# MayKhoan.net
KiCad netlist of a schematic drawn in EasyEDA Pro
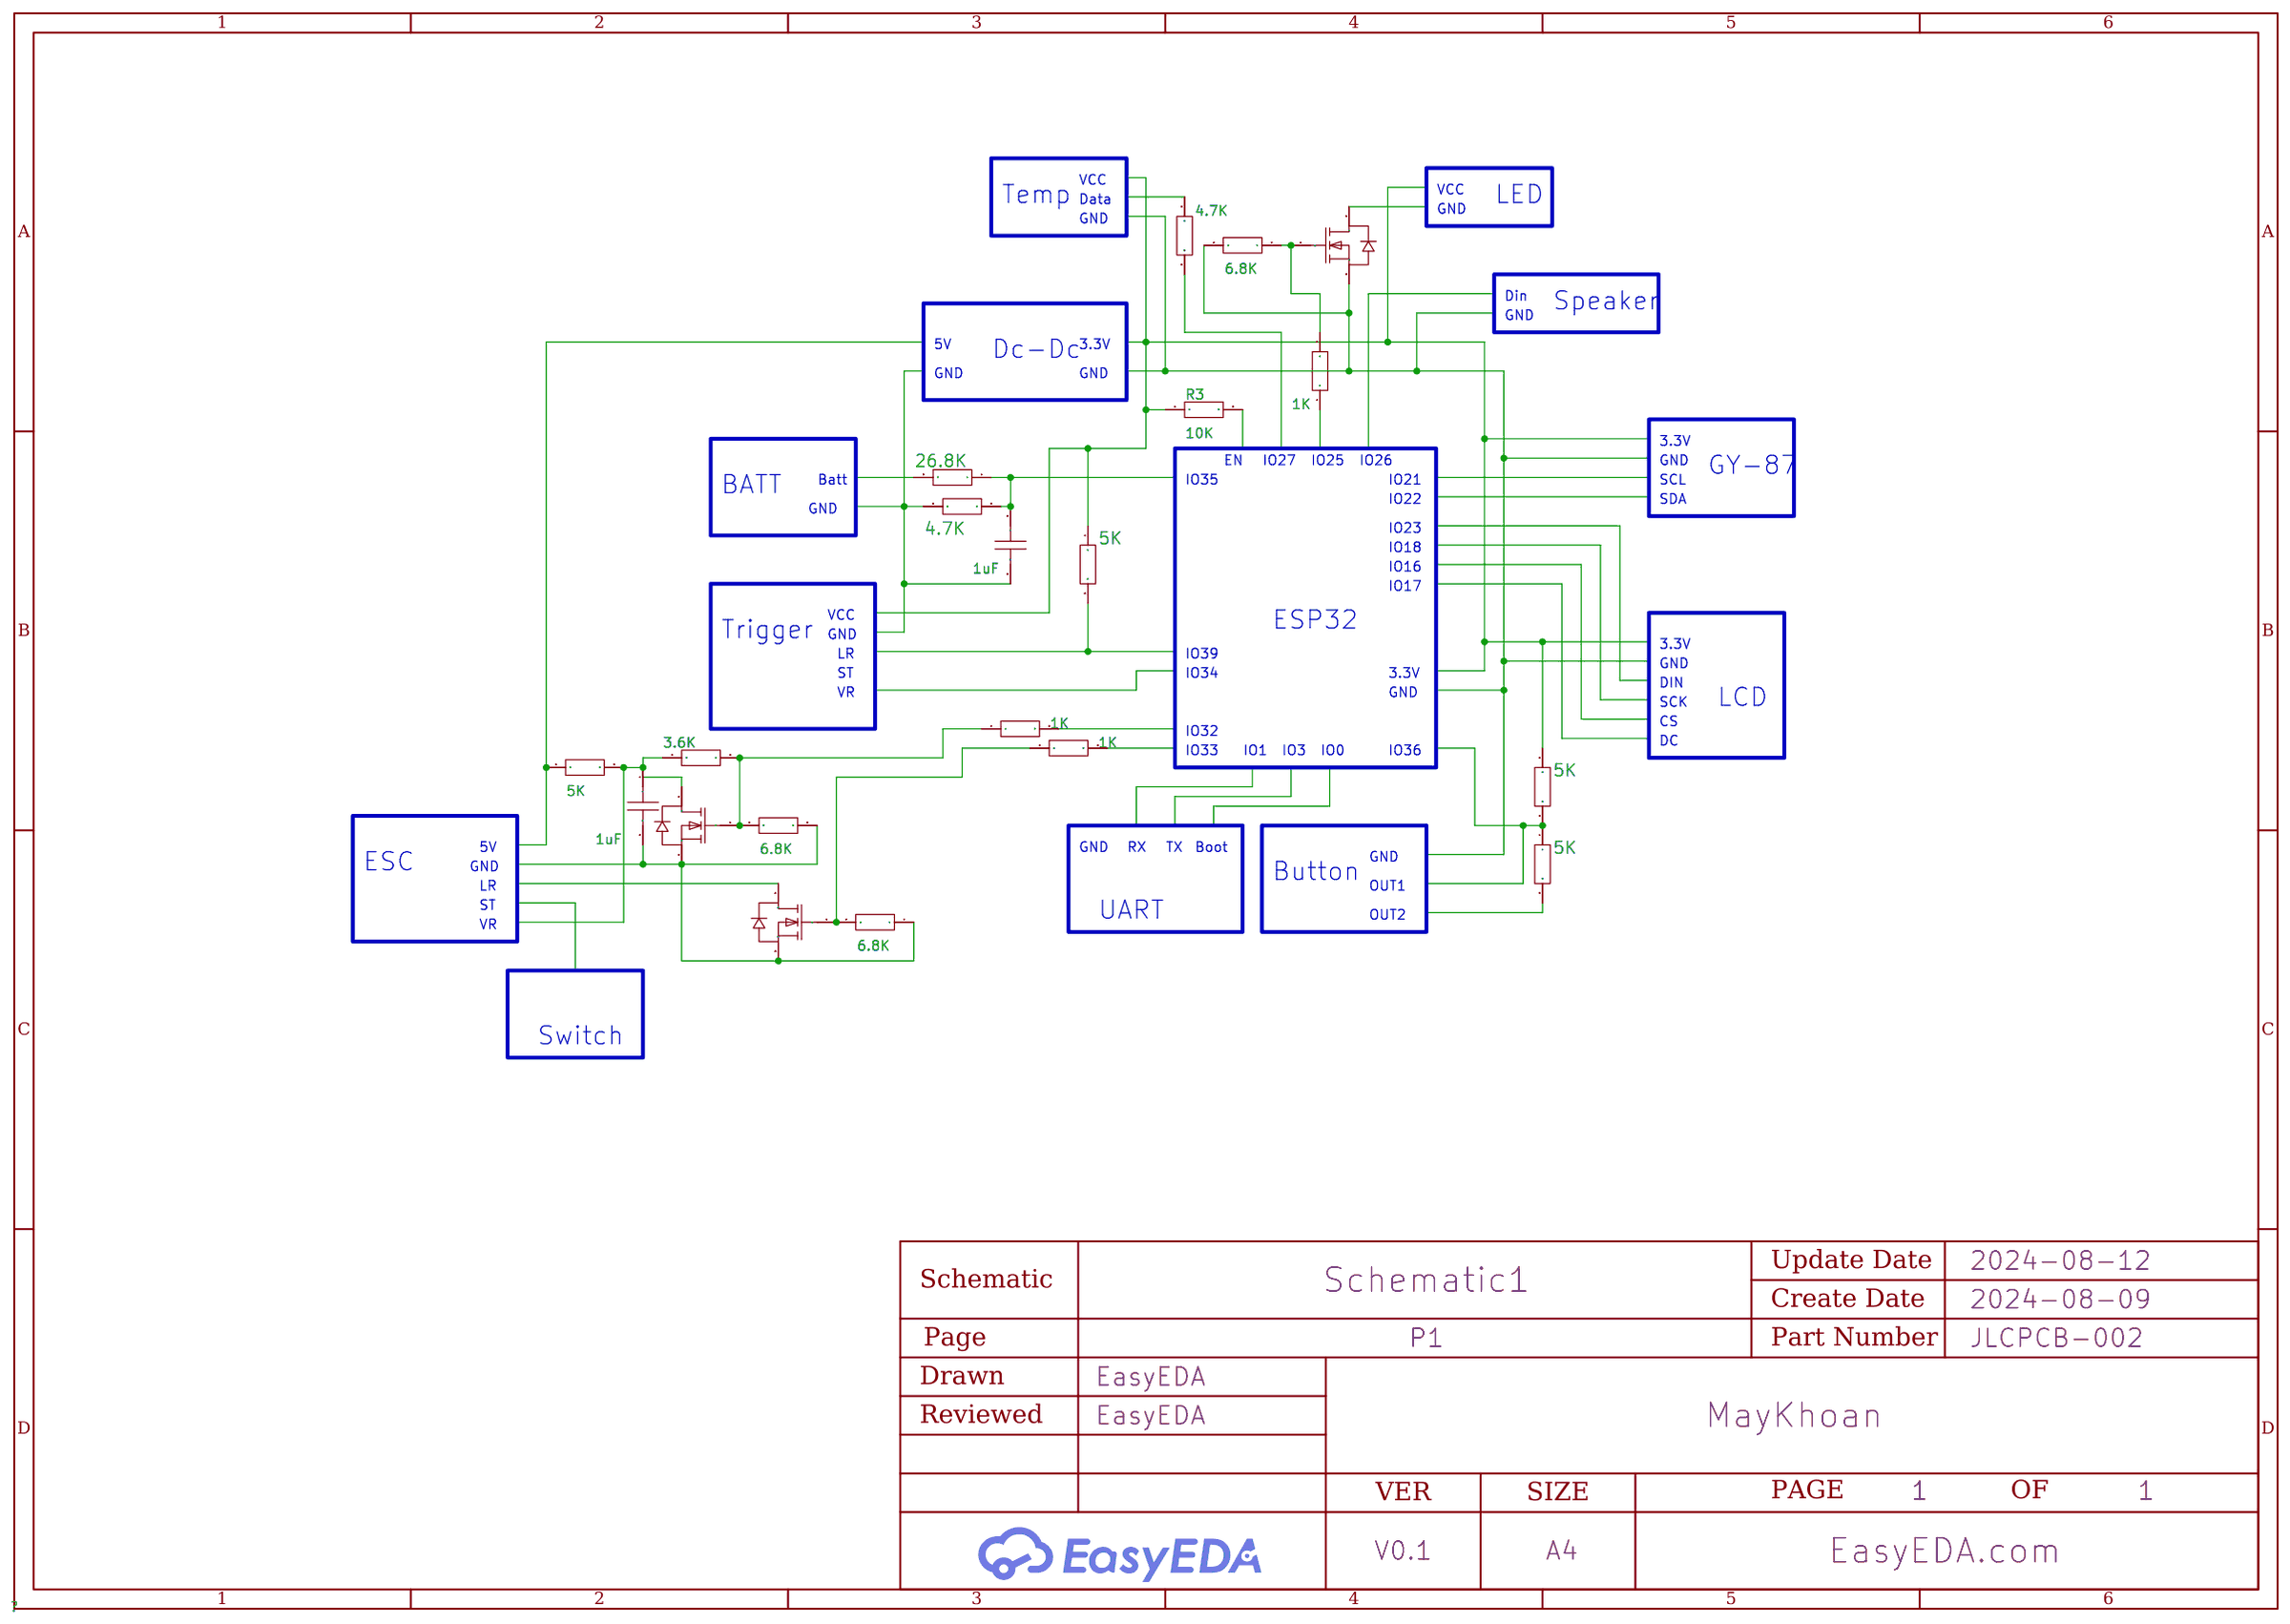
[diagram p0: schematic sheet]

(export (version "E")
  (design (tool "Eeschema 10.0.6"))
  (components
    (comp (ref "C1") (value "1uF") (footprint "easyedapro:C0603") (libsource (lib "easyedapro") (part "CAP")))
    (comp (ref "C2") (value "1uF") (footprint "easyedapro:C0603") (libsource (lib "easyedapro") (part "CAP")))
    (comp (ref "R1")
      (value "4.7K")
      (footprint "easyedapro:R0603")
      (libsource (lib "easyedapro") (part "Res"))
    )
    (comp (ref "R2")
      (value "26.8K")
      (footprint "easyedapro:R0603")
      (libsource (lib "easyedapro") (part "Res"))
    )
    (comp (ref "R3") (value "10K") (footprint "easyedapro:R0603") (libsource (lib "easyedapro") (part "Res")))
    (comp (ref "R4") (value "5K") (footprint "easyedapro:R0603") (libsource (lib "easyedapro") (part "Res")))
    (comp (ref "R5")
      (value "3.6K")
      (footprint "easyedapro:R0603")
      (libsource (lib "easyedapro") (part "Res"))
    )
    (comp (ref "R6") (value "5K") (footprint "easyedapro:R0603") (libsource (lib "easyedapro") (part "Res")))
    (comp (ref "R7")
      (value "6.8K")
      (footprint "easyedapro:R0603")
      (libsource (lib "easyedapro") (part "Res"))
    )
    (comp (ref "R8")
      (value "6.8K")
      (footprint "easyedapro:R0603")
      (libsource (lib "easyedapro") (part "Res"))
    )
    (comp (ref "R10") (value "5K") (footprint "easyedapro:R0603") (libsource (lib "easyedapro") (part "Res")))
    (comp (ref "R11") (value "5K") (footprint "easyedapro:R0603") (libsource (lib "easyedapro") (part "Res")))
    (comp (ref "R12")
      (value "6.8K")
      (footprint "easyedapro:R0603")
      (libsource (lib "easyedapro") (part "Res"))
    )
    (comp (ref "R14") (value "1K") (footprint "easyedapro:R0603") (libsource (lib "easyedapro") (part "Res")))
    (comp (ref "R15") (value "1K") (footprint "easyedapro:R0603") (libsource (lib "easyedapro") (part "Res")))
    (comp (ref "R16") (value "1K") (footprint "easyedapro:R0603") (libsource (lib "easyedapro") (part "Res")))
    (comp (ref "R17")
      (value "4.7K")
      (footprint "easyedapro:R0603")
      (libsource (lib "easyedapro") (part "Res"))
    )
    (comp (ref "U1")
      (value "GC2M0080120D")
      (footprint "easyedapro:TO-247-3_L15.8-W5.0-P5.44-L")
      (fields (field (name "Manufacturer") "SUPSiC(国晶微半导体)"))
      (libsource (lib "easyedapro") (part "GC2M0080120D"))
    )
    (comp (ref "U2")
      (value "GC2M0080120D")
      (footprint "easyedapro:TO-247-3_L15.8-W5.0-P5.44-L")
      (fields (field (name "Manufacturer") "SUPSiC(国晶微半导体)"))
      (libsource (lib "easyedapro") (part "GC2M0080120D"))
    )
    (comp (ref "U4")
      (value "GC2M0080120D")
      (footprint "easyedapro:TO-247-3_L15.8-W5.0-P5.44-L")
      (fields (field (name "Manufacturer") "SUPSiC(国晶微半导体)"))
      (libsource (lib "easyedapro") (part "GC2M0080120D"))
    )
  )
  (nets
    (net (code "1") (name "Net-(C2-Pad1)") (class "Default")
      (node (ref "C2") (pin "1") (pinfunction "1_1") (pintype "input"))
      (node (ref "R1") (pin "1") (pinfunction "1_1") (pintype "input"))
      (node (ref "R2") (pin "1") (pinfunction "1_1") (pintype "input"))
    )
    (net (code "2") (name "Net-(C2-Pad2)") (class "Default")
      (node (ref "C2") (pin "2") (pinfunction "2_2") (pintype "input"))
      (node (ref "R1") (pin "2") (pinfunction "2_2") (pintype "input"))
    )
    (net (code "3") (name "Net-(R10-Pad1)") (class "Default")
      (node (ref "R10") (pin "1") (pinfunction "1_1") (pintype "input"))
      (node (ref "R11") (pin "2") (pinfunction "2_2") (pintype "input"))
    )
    (net (code "4") (name "Net-(R11-Pad1)") (class "Default")
      (node (ref "R11") (pin "1") (pinfunction "1_1") (pintype "input"))
      (node (ref "R3") (pin "1") (pinfunction "1_1") (pintype "input"))
      (node (ref "R4") (pin "1") (pinfunction "1_1") (pintype "input"))
    )
    (net (code "5") (name "Net-(U1-G)") (class "Default")
      (node (ref "R14") (pin "1") (pinfunction "1_1") (pintype "input"))
      (node (ref "R8") (pin "2") (pinfunction "2_2") (pintype "input"))
      (node (ref "U1") (pin "1") (pinfunction "G_1") (pintype "unspecified"))
    )
    (net (code "6") (name "Net-(U1-S)") (class "Default")
      (node (ref "C1") (pin "2") (pinfunction "2_2") (pintype "input"))
      (node (ref "R7") (pin "1") (pinfunction "1_1") (pintype "input"))
      (node (ref "R8") (pin "1") (pinfunction "1_1") (pintype "input"))
      (node (ref "U1") (pin "3") (pinfunction "S_3") (pintype "unspecified"))
      (node (ref "U2") (pin "3") (pinfunction "S_3") (pintype "unspecified"))
    )
    (net (code "7") (name "Net-(U2-D)") (class "Default")
      (node (ref "C1") (pin "1") (pinfunction "1_1") (pintype "input"))
      (node (ref "R5") (pin "1") (pinfunction "1_1") (pintype "input"))
      (node (ref "R6") (pin "2") (pinfunction "2_2") (pintype "input"))
      (node (ref "U2") (pin "2") (pinfunction "D_2") (pintype "unspecified"))
    )
    (net (code "8") (name "Net-(U2-G)") (class "Default")
      (node (ref "R15") (pin "1") (pinfunction "1_1") (pintype "input"))
      (node (ref "R5") (pin "2") (pinfunction "2_2") (pintype "input"))
      (node (ref "R7") (pin "2") (pinfunction "2_2") (pintype "input"))
      (node (ref "U2") (pin "1") (pinfunction "G_1") (pintype "unspecified"))
    )
    (net (code "9") (name "Net-(U4-G)") (class "Default")
      (node (ref "R12") (pin "1") (pinfunction "1_1") (pintype "input"))
      (node (ref "R16") (pin "2") (pinfunction "2_2") (pintype "input"))
      (node (ref "U4") (pin "1") (pinfunction "G_1") (pintype "unspecified"))
    )
    (net (code "10") (name "Net-(U4-S)") (class "Default")
      (node (ref "R12") (pin "2") (pinfunction "2_2") (pintype "input"))
      (node (ref "U4") (pin "3") (pinfunction "S_3") (pintype "unspecified"))
    )
    (net (code "11") (name "unconnected-(R2-Pad2)") (class "Default")
      (node (ref "R2") (pin "2") (pinfunction "2_2") (pintype "input"))
    )
    (net (code "12") (name "unconnected-(R3-Pad2)") (class "Default")
      (node (ref "R3") (pin "2") (pinfunction "2_2") (pintype "input"))
    )
    (net (code "13") (name "unconnected-(R4-Pad2)") (class "Default")
      (node (ref "R4") (pin "2") (pinfunction "2_2") (pintype "input"))
    )
    (net (code "14") (name "unconnected-(R6-Pad1)") (class "Default")
      (node (ref "R6") (pin "1") (pinfunction "1_1") (pintype "input"))
    )
    (net (code "15") (name "unconnected-(R10-Pad2)") (class "Default")
      (node (ref "R10") (pin "2") (pinfunction "2_2") (pintype "input"))
    )
    (net (code "16") (name "unconnected-(R14-Pad2)") (class "Default")
      (node (ref "R14") (pin "2") (pinfunction "2_2") (pintype "input"))
    )
    (net (code "17") (name "unconnected-(R15-Pad2)") (class "Default")
      (node (ref "R15") (pin "2") (pinfunction "2_2") (pintype "input"))
    )
    (net (code "18") (name "unconnected-(R16-Pad1)") (class "Default")
      (node (ref "R16") (pin "1") (pinfunction "1_1") (pintype "input"))
    )
    (net (code "19") (name "unconnected-(R17-Pad1)") (class "Default")
      (node (ref "R17") (pin "1") (pinfunction "1_1") (pintype "input"))
    )
    (net (code "20") (name "unconnected-(R17-Pad2)") (class "Default")
      (node (ref "R17") (pin "2") (pinfunction "2_2") (pintype "input"))
    )
    (net (code "21") (name "unconnected-(U1-D-Pad2)") (class "Default")
      (node (ref "U1") (pin "2") (pinfunction "D_2") (pintype "unspecified"))
    )
    (net (code "22") (name "unconnected-(U4-D-Pad2)") (class "Default")
      (node (ref "U4") (pin "2") (pinfunction "D_2") (pintype "unspecified"))
    )
  )
)
